# Adafruit_MEMENTO_Camera_Board.net
KiCad netlist of a schematic drawn in EAGLE
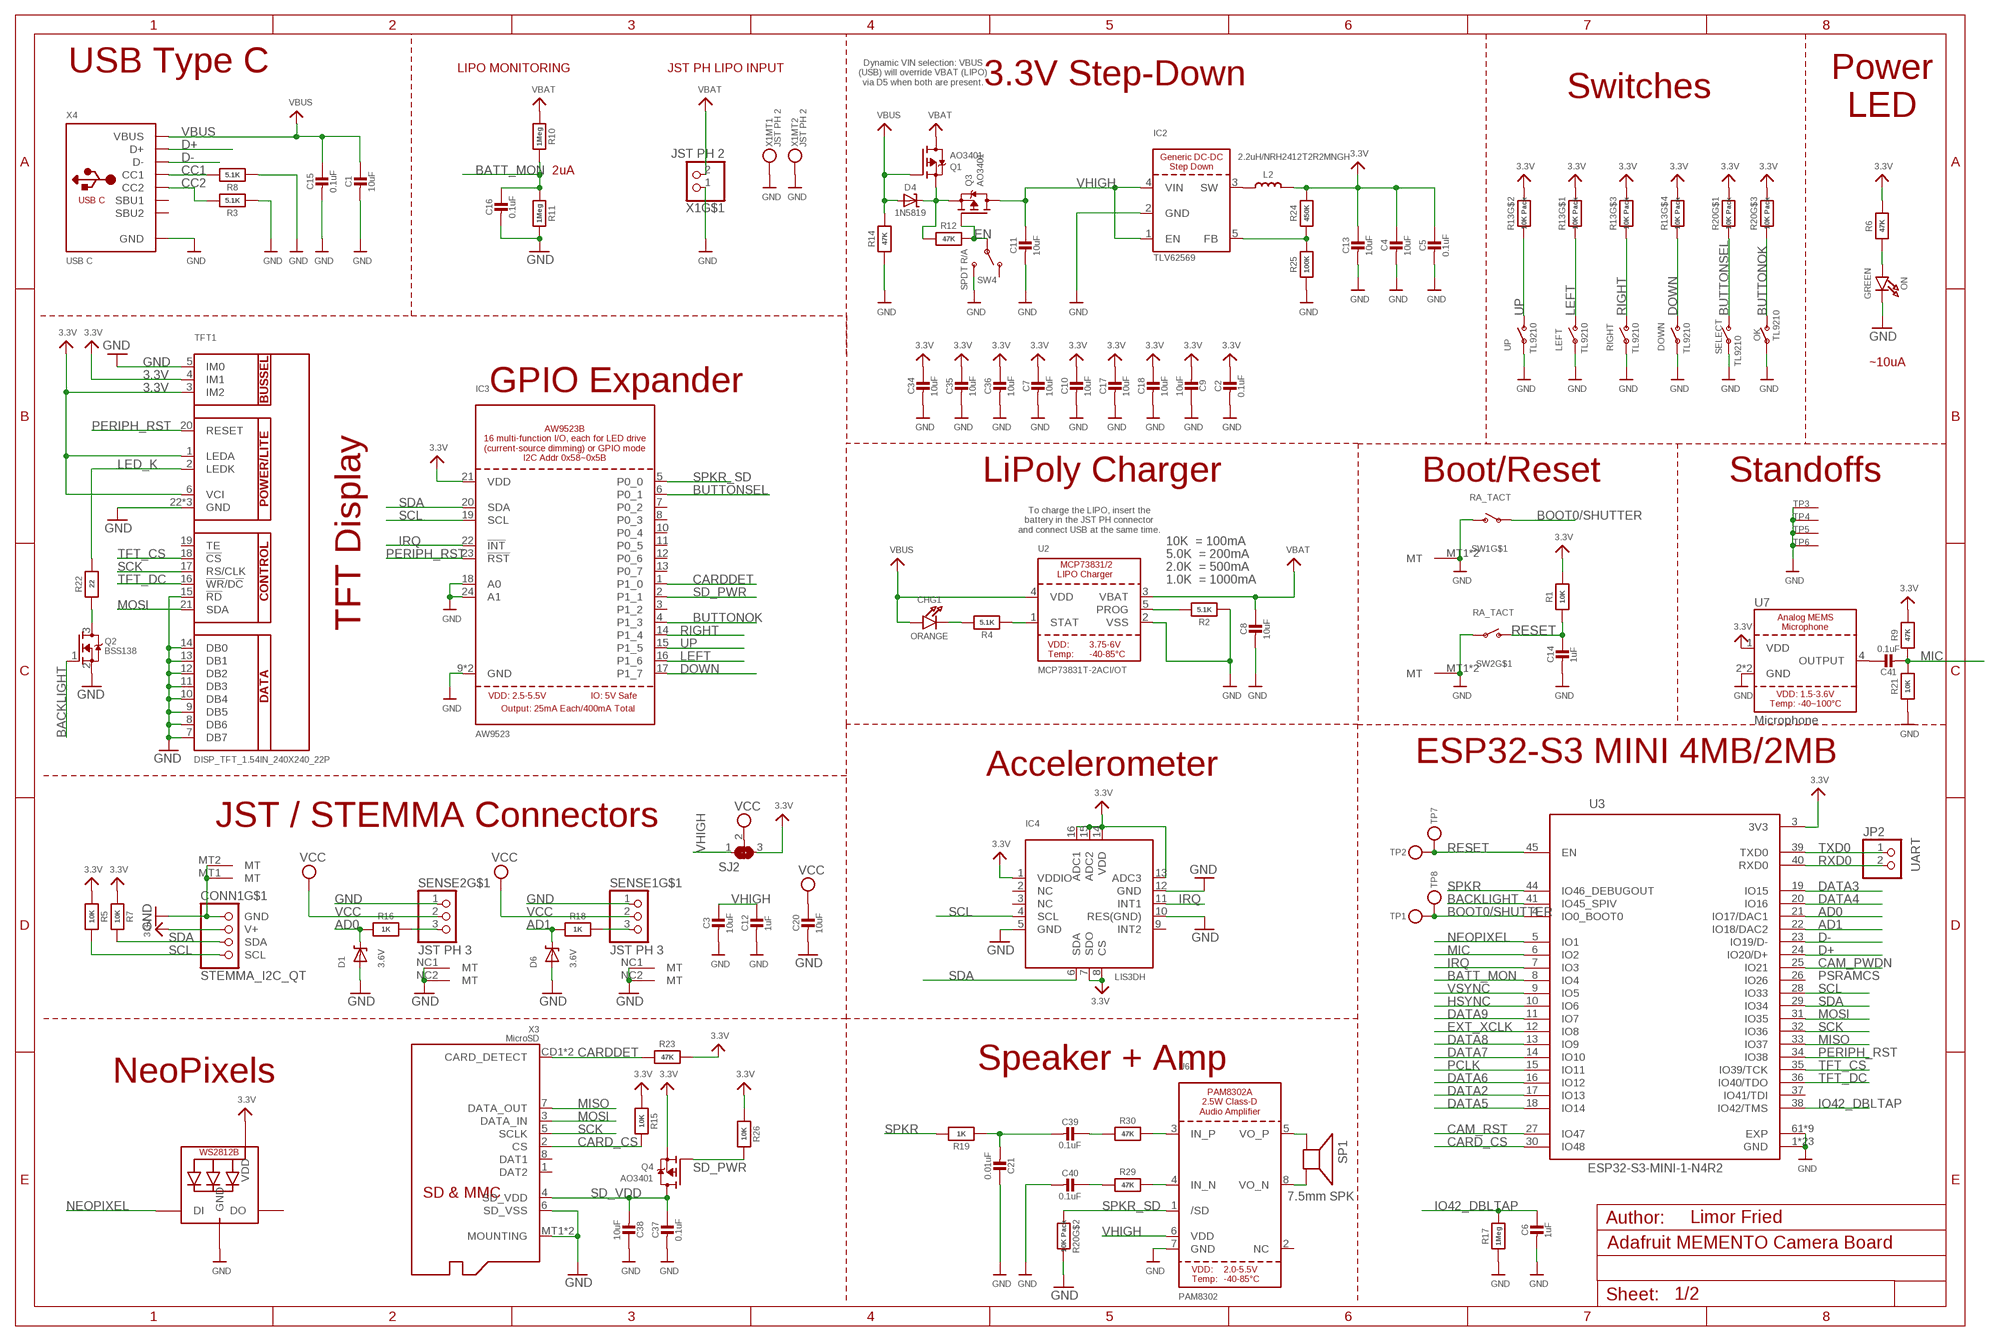
[diagram p0: schematic, sheet 1]
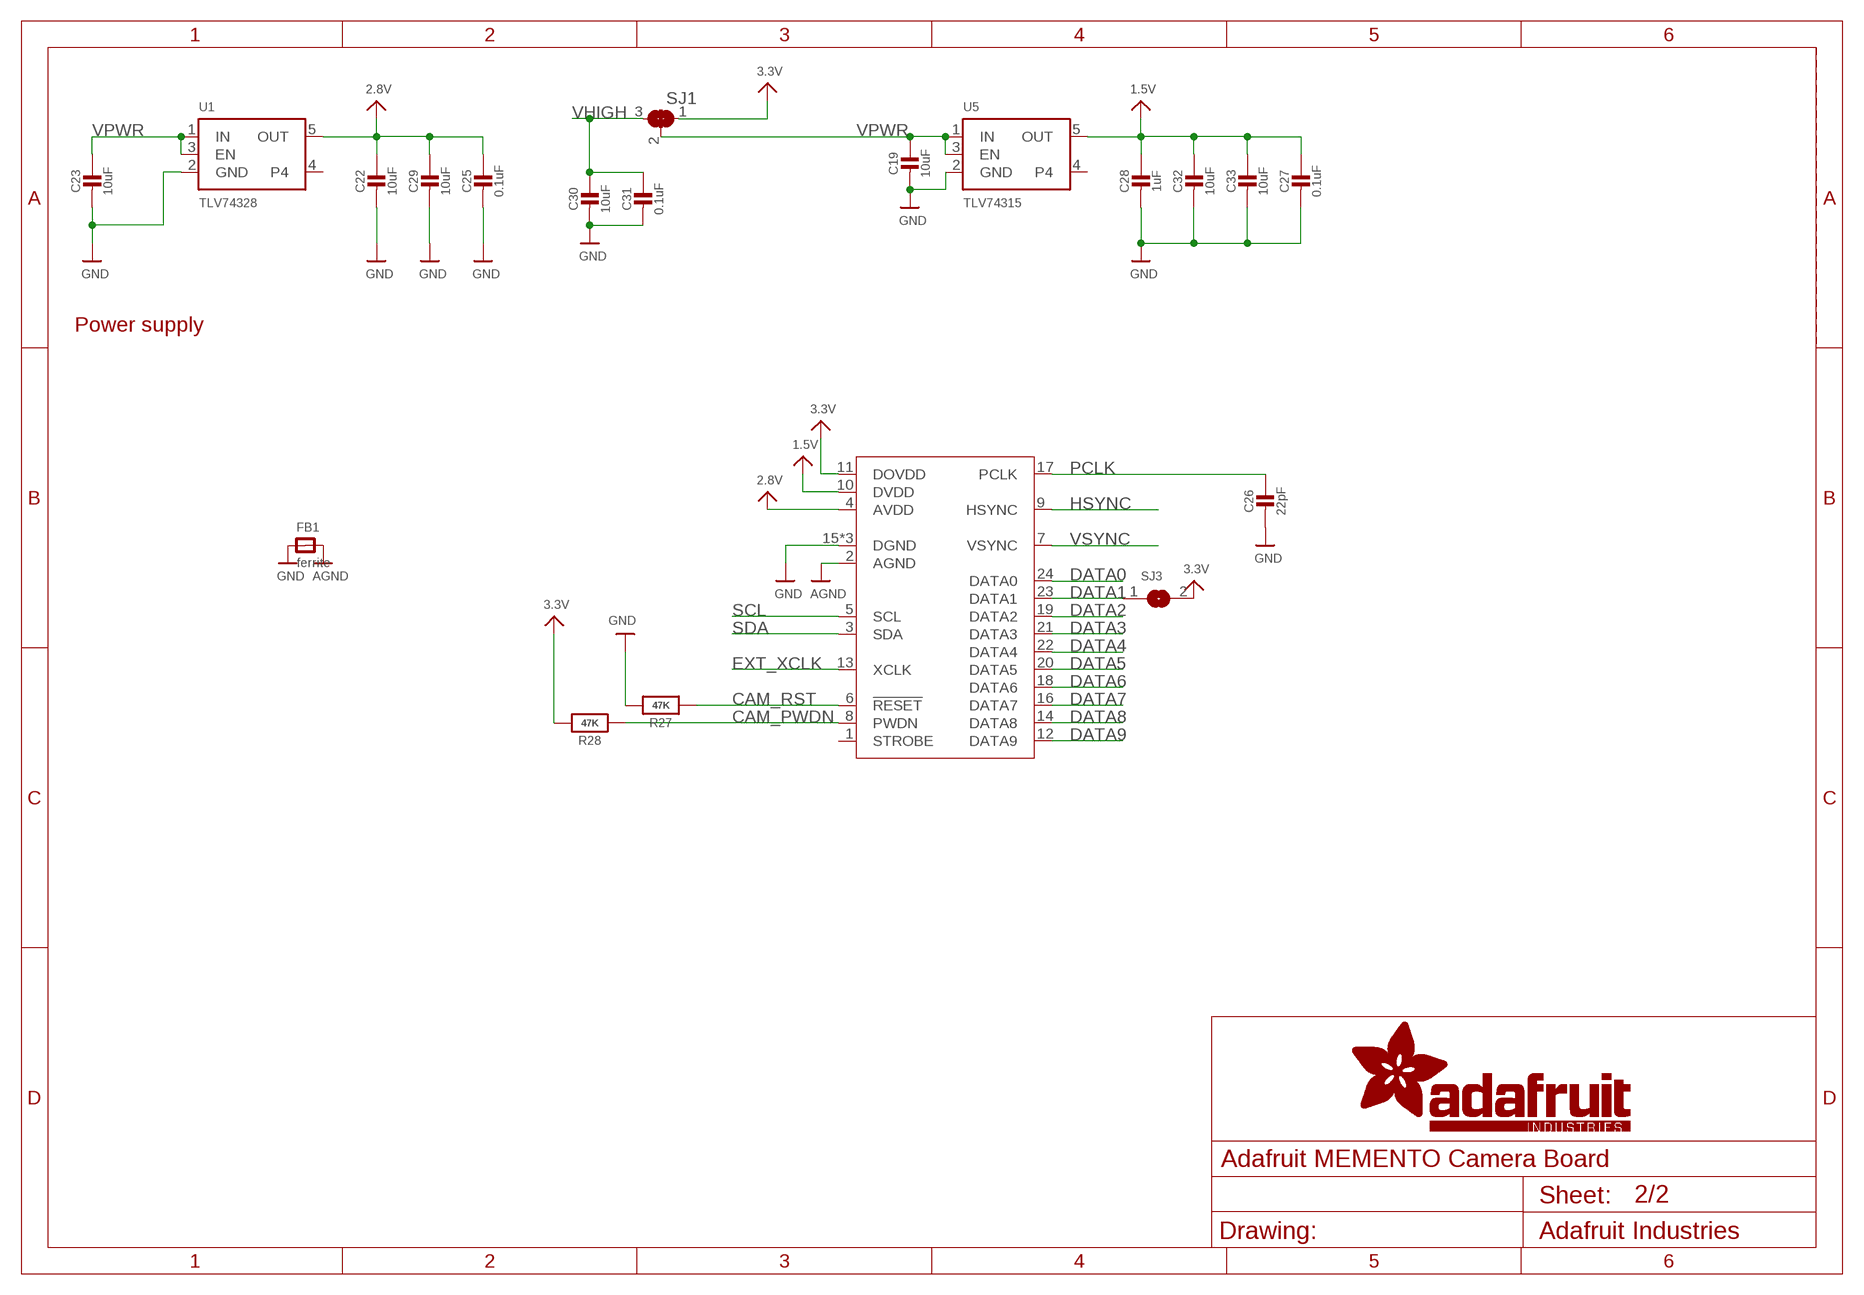
[diagram p1: schematic, sheet 2]

(export (version "E")
  (design (tool "Eeschema 10.0.6"))
  (components
    (comp (ref "C19")
      (value "10uF")
      (footprint "eagle-import:0805-NO")
      (libsource (lib "eagle-import") (part "CAP_CERAMIC0805-NOOUTLINE"))
    )
    (comp (ref "C22")
      (value "10uF")
      (footprint "eagle-import:0805-NO")
      (libsource (lib "eagle-import") (part "CAP_CERAMIC0805-NOOUTLINE"))
    )
    (comp (ref "C23")
      (value "10uF")
      (footprint "eagle-import:0805-NO")
      (libsource (lib "eagle-import") (part "CAP_CERAMIC0805-NOOUTLINE"))
    )
    (comp (ref "C25")
      (value "0.1uF")
      (footprint "eagle-import:0603-NO")
      (libsource (lib "eagle-import") (part "CAP_CERAMIC0603_NO"))
    )
    (comp (ref "C26")
      (value "22pF")
      (footprint "eagle-import:0603-NO")
      (libsource (lib "eagle-import") (part "CAP_CERAMIC0603_NO"))
    )
    (comp (ref "C27")
      (value "0.1uF")
      (footprint "eagle-import:0603-NO")
      (libsource (lib "eagle-import") (part "CAP_CERAMIC0603_NO"))
    )
    (comp (ref "C28")
      (value "1uF")
      (footprint "eagle-import:0603-NO")
      (libsource (lib "eagle-import") (part "CAP_CERAMIC0603_NO"))
    )
    (comp (ref "C29")
      (value "10uF")
      (footprint "eagle-import:0805-NO")
      (libsource (lib "eagle-import") (part "CAP_CERAMIC0805-NOOUTLINE"))
    )
    (comp (ref "C30")
      (value "10uF")
      (footprint "eagle-import:0805-NO")
      (libsource (lib "eagle-import") (part "CAP_CERAMIC0805-NOOUTLINE"))
    )
    (comp (ref "C31")
      (value "0.1uF")
      (footprint "eagle-import:0603-NO")
      (libsource (lib "eagle-import") (part "CAP_CERAMIC0603_NO"))
    )
    (comp (ref "C32")
      (value "10uF")
      (footprint "eagle-import:0805-NO")
      (libsource (lib "eagle-import") (part "CAP_CERAMIC0805-NOOUTLINE"))
    )
    (comp (ref "C33")
      (value "10uF")
      (footprint "eagle-import:0805-NO")
      (libsource (lib "eagle-import") (part "CAP_CERAMIC0805-NOOUTLINE"))
    )
    (comp (ref "FB1")
      (value "ferrite")
      (footprint "eagle-import:0603-NO")
      (libsource (lib "eagle-import") (part "FERRITE-0603NO"))
    )
    (comp (ref "R27")
      (value "47K")
      (footprint "eagle-import:0603-NO")
      (libsource (lib "eagle-import") (part "RESISTOR_0603_NOOUT"))
    )
    (comp (ref "R28")
      (value "47K")
      (footprint "eagle-import:0603-NO")
      (libsource (lib "eagle-import") (part "RESISTOR_0603_NOOUT"))
    )
    (comp (ref "SJ1")
      (value "SOLDERJUMPER_2WAY")
      (footprint "eagle-import:SOLDERJUMPER_2WAY_OPEN_NOPASTE")
      (libsource (lib "eagle-import") (part "SOLDERJUMPER_2WAY"))
    )
    (comp (ref "SJ3")
      (value "SOLDERJUMPERCLOSED")
      (footprint "eagle-import:SOLDERJUMPER_CLOSEDWIRE")
      (libsource (lib "eagle-import") (part "SOLDERJUMPERCLOSED"))
    )
    (comp (ref "U1")
      (value "TLV74328")
      (footprint "eagle-import:SOT23-5")
      (fields (field (name "JLC_ROTATION") "0"))
      (libsource (lib "eagle-import") (part "VREG_SOT23-5"))
    )
    (comp (ref "U5")
      (value "TLV74315")
      (footprint "eagle-import:SOT23-5")
      (fields (field (name "JLC_ROTATION") "0"))
      (libsource (lib "eagle-import") (part "VREG_SOT23-5"))
    )
    (comp (ref "X2")
      (value "CAMERA_OV2640")
      (footprint "eagle-import:OV2640FSL")
      (libsource (lib "eagle-import") (part "CAMERA_OV2640"))
    )
    (comp (ref "C1")
      (value "10uF")
      (footprint "eagle-import:0805-NO")
      (libsource (lib "eagle-import") (part "CAP_CERAMIC0805-NOOUTLINE"))
    )
    (comp (ref "C2")
      (value "0.1uF")
      (footprint "eagle-import:0603-NO")
      (libsource (lib "eagle-import") (part "CAP_CERAMIC0603_NO"))
    )
    (comp (ref "C3")
      (value "10uF")
      (footprint "eagle-import:0805-NO")
      (libsource (lib "eagle-import") (part "CAP_CERAMIC0805-NOOUTLINE"))
    )
    (comp (ref "C4")
      (value "10uF")
      (footprint "eagle-import:0805-NO")
      (libsource (lib "eagle-import") (part "CAP_CERAMIC0805-NOOUTLINE"))
    )
    (comp (ref "C5")
      (value "0.1uF")
      (footprint "eagle-import:0603-NO")
      (libsource (lib "eagle-import") (part "CAP_CERAMIC0603_NO"))
    )
    (comp (ref "C6")
      (value "1uF")
      (footprint "eagle-import:0603-NO")
      (libsource (lib "eagle-import") (part "CAP_CERAMIC0603_NO"))
    )
    (comp (ref "C7")
      (value "10uF")
      (footprint "eagle-import:0805-NO")
      (libsource (lib "eagle-import") (part "CAP_CERAMIC0805-NOOUTLINE"))
    )
    (comp (ref "C8")
      (value "10uF")
      (footprint "eagle-import:0805-NO")
      (libsource (lib "eagle-import") (part "CAP_CERAMIC0805-NOOUTLINE"))
    )
    (comp (ref "C9")
      (value "10uF")
      (footprint "eagle-import:0805-NO")
      (libsource (lib "eagle-import") (part "CAP_CERAMIC0805-NOOUTLINE"))
    )
    (comp (ref "C10")
      (value "10uF")
      (footprint "eagle-import:0805-NO")
      (libsource (lib "eagle-import") (part "CAP_CERAMIC0805-NOOUTLINE"))
    )
    (comp (ref "C11")
      (value "10uF")
      (footprint "eagle-import:0805-NO")
      (libsource (lib "eagle-import") (part "CAP_CERAMIC0805-NOOUTLINE"))
    )
    (comp (ref "C12")
      (value "1uF")
      (footprint "eagle-import:0603-NO")
      (libsource (lib "eagle-import") (part "CAP_CERAMIC0603_NO"))
    )
    (comp (ref "C13")
      (value "10uF")
      (footprint "eagle-import:0805-NO")
      (libsource (lib "eagle-import") (part "CAP_CERAMIC0805-NOOUTLINE"))
    )
    (comp (ref "C14")
      (value "1uF")
      (footprint "eagle-import:0603-NO")
      (libsource (lib "eagle-import") (part "CAP_CERAMIC0603_NO"))
    )
    (comp (ref "C15")
      (value "0.1uF")
      (footprint "eagle-import:0603-NO")
      (libsource (lib "eagle-import") (part "CAP_CERAMIC0603_NO"))
    )
    (comp (ref "C16")
      (value "0.1uF")
      (footprint "eagle-import:0603-NO")
      (libsource (lib "eagle-import") (part "CAP_CERAMIC0603_NO"))
    )
    (comp (ref "C17")
      (value "10uF")
      (footprint "eagle-import:0805-NO")
      (libsource (lib "eagle-import") (part "CAP_CERAMIC0805-NOOUTLINE"))
    )
    (comp (ref "C18")
      (value "10uF")
      (footprint "eagle-import:0805-NO")
      (libsource (lib "eagle-import") (part "CAP_CERAMIC0805-NOOUTLINE"))
    )
    (comp (ref "C20")
      (value "10uF")
      (footprint "eagle-import:0805-NO")
      (libsource (lib "eagle-import") (part "CAP_CERAMIC0805-NOOUTLINE"))
    )
    (comp (ref "C21")
      (value "0.01uF")
      (footprint "eagle-import:0603-NO")
      (libsource (lib "eagle-import") (part "CAP_CERAMIC0603_NO"))
    )
    (comp (ref "C34")
      (value "10uF")
      (footprint "eagle-import:0805-NO")
      (libsource (lib "eagle-import") (part "CAP_CERAMIC0805-NOOUTLINE"))
    )
    (comp (ref "C35")
      (value "10uF")
      (footprint "eagle-import:0805-NO")
      (libsource (lib "eagle-import") (part "CAP_CERAMIC0805-NOOUTLINE"))
    )
    (comp (ref "C36")
      (value "10uF")
      (footprint "eagle-import:0805-NO")
      (libsource (lib "eagle-import") (part "CAP_CERAMIC0805-NOOUTLINE"))
    )
    (comp (ref "C37")
      (value "0.1uF")
      (footprint "eagle-import:0603-NO")
      (libsource (lib "eagle-import") (part "CAP_CERAMIC0603_NO"))
    )
    (comp (ref "C38")
      (value "10uF")
      (footprint "eagle-import:0805-NO")
      (libsource (lib "eagle-import") (part "CAP_CERAMIC0805-NOOUTLINE"))
    )
    (comp (ref "C39")
      (value "0.1uF")
      (footprint "eagle-import:0603-NO")
      (libsource (lib "eagle-import") (part "CAP_CERAMIC0603_NO"))
    )
    (comp (ref "C40")
      (value "0.1uF")
      (footprint "eagle-import:0603-NO")
      (libsource (lib "eagle-import") (part "CAP_CERAMIC0603_NO"))
    )
    (comp (ref "C41")
      (value "0.1uF")
      (footprint "eagle-import:0603-NO")
      (libsource (lib "eagle-import") (part "CAP_CERAMIC0603_NO"))
    )
    (comp (ref "CHG1")
      (value "ORANGE")
      (footprint "eagle-import:CHIPLED_0603_NOOUTLINE")
      (libsource (lib "eagle-import") (part "LED0603_NOOUTLINE"))
    )
    (comp (ref "CONN1")
      (value "STEMMA_I2C_QT")
      (footprint "eagle-import:JST_SH4")
      (libsource (lib "eagle-import") (part "STEMMA_I2C_QT"))
    )
    (comp (ref "D1")
      (value "3.6V")
      (footprint "eagle-import:SOD-323")
      (libsource (lib "eagle-import") (part "DIODE-ZENERSOD323"))
    )
    (comp (ref "D4")
      (value "1N5819")
      (footprint "eagle-import:SOD-123")
      (libsource (lib "eagle-import") (part "DIODE-SCHOTTKYSOD-123"))
    )
    (comp (ref "D6")
      (value "3.6V")
      (footprint "eagle-import:SOD-323")
      (libsource (lib "eagle-import") (part "DIODE-ZENERSOD323"))
    )
    (comp (ref "DOWN")
      (value "TL9210")
      (footprint "eagle-import:TL9210")
      (libsource (lib "eagle-import") (part "SWITCH_SPST_NOMNT_TL9210"))
    )
    (comp (ref "IC2")
      (value "TLV62569")
      (footprint "eagle-import:SOT23-5")
      (libsource (lib "eagle-import") (part "VREG_BUCK_5PIN_AP3429/A"))
    )
    (comp (ref "IC3")
      (value "AW9523")
      (footprint "eagle-import:QFN24_4MM_SMSC")
      (libsource (lib "eagle-import") (part "AW9523"))
    )
    (comp (ref "IC4")
      (value "LIS3DH")
      (footprint "eagle-import:LGA16_3X3MM")
      (libsource (lib "eagle-import") (part "ACCEL_LIS3DHTR"))
    )
    (comp (ref "JP2")
      (value "UART")
      (footprint "eagle-import:1X02_ROUND")
      (libsource (lib "eagle-import") (part "HEADER-1X2ROUND"))
    )
    (comp (ref "L2")
      (value "2.2uH/NRH2412T2R2MNGH")
      (footprint "eagle-import:INDUCTOR_TAIYOYUDEN_NR3015")
      (libsource (lib "eagle-import") (part "INDUCTORNR3015"))
    )
    (comp (ref "LED2")
      (value "WS2812B_SK6805_1515")
      (footprint "eagle-import:SK6805_1515")
      (libsource (lib "eagle-import") (part "WS2812B_SK6805_1515"))
    )
    (comp (ref "LEFT")
      (value "TL9210")
      (footprint "eagle-import:TL9210")
      (libsource (lib "eagle-import") (part "SWITCH_SPST_NOMNT_TL9210"))
    )
    (comp (ref "OK")
      (value "TL9210")
      (footprint "eagle-import:TL9210")
      (libsource (lib "eagle-import") (part "SWITCH_SPST_NOMNT_TL9210"))
    )
    (comp (ref "ON")
      (value "GREEN")
      (footprint "eagle-import:CHIPLED_0603_NOOUTLINE")
      (libsource (lib "eagle-import") (part "LED0603_NOOUTLINE"))
    )
    (comp (ref "Q1")
      (value "AO3401")
      (footprint "eagle-import:SOT23-R")
      (libsource (lib "eagle-import") (part "MOSFET-P"))
    )
    (comp (ref "Q2")
      (value "BSS138")
      (footprint "eagle-import:SOT23-WIDE")
      (libsource (lib "eagle-import") (part "MOSFET-NWIDE"))
    )
    (comp (ref "Q3")
      (value "AO3401")
      (footprint "eagle-import:SOT23-R")
      (libsource (lib "eagle-import") (part "MOSFET-P"))
    )
    (comp (ref "Q4")
      (value "AO3401")
      (footprint "eagle-import:SOT23-R")
      (libsource (lib "eagle-import") (part "MOSFET-P"))
    )
    (comp (ref "R1")
      (value "10K")
      (footprint "eagle-import:0603-NO")
      (libsource (lib "eagle-import") (part "RESISTOR_0603_NOOUT"))
    )
    (comp (ref "R2")
      (value "5.1K")
      (footprint "eagle-import:0603-NO")
      (libsource (lib "eagle-import") (part "RESISTOR_0603_NOOUT"))
    )
    (comp (ref "R3")
      (value "5.1K")
      (footprint "eagle-import:0603-NO")
      (libsource (lib "eagle-import") (part "RESISTOR_0603_NOOUT"))
    )
    (comp (ref "R4")
      (value "5.1K")
      (footprint "eagle-import:0603-NO")
      (libsource (lib "eagle-import") (part "RESISTOR_0603_NOOUT"))
    )
    (comp (ref "R5")
      (value "10K")
      (footprint "eagle-import:0603-NO")
      (libsource (lib "eagle-import") (part "RESISTOR_0603_NOOUT"))
    )
    (comp (ref "R6")
      (value "47K")
      (footprint "eagle-import:0603-NO")
      (libsource (lib "eagle-import") (part "RESISTOR_0603_NOOUT"))
    )
    (comp (ref "R7")
      (value "10K")
      (footprint "eagle-import:0603-NO")
      (libsource (lib "eagle-import") (part "RESISTOR_0603_NOOUT"))
    )
    (comp (ref "R8")
      (value "5.1K")
      (footprint "eagle-import:0603-NO")
      (libsource (lib "eagle-import") (part "RESISTOR_0603_NOOUT"))
    )
    (comp (ref "R9")
      (value "47K")
      (footprint "eagle-import:0603-NO")
      (libsource (lib "eagle-import") (part "RESISTOR_0603_NOOUT"))
    )
    (comp (ref "R10")
      (value "1Meg")
      (footprint "eagle-import:0603-NO")
      (libsource (lib "eagle-import") (part "RESISTOR_0603_NOOUT"))
    )
    (comp (ref "R11")
      (value "1Meg")
      (footprint "eagle-import:0603-NO")
      (libsource (lib "eagle-import") (part "RESISTOR_0603_NOOUT"))
    )
    (comp (ref "R12")
      (value "47K")
      (footprint "eagle-import:0603-NO")
      (libsource (lib "eagle-import") (part "RESISTOR_0603_NOOUT"))
    )
    (comp (ref "R13")
      (value "10K Pack")
      (footprint "eagle-import:RESPACK_4X0603")
      (libsource (lib "eagle-import") (part "RESISTOR_4PACK"))
    )
    (comp (ref "R14")
      (value "47K")
      (footprint "eagle-import:0603-NO")
      (libsource (lib "eagle-import") (part "RESISTOR_0603_NOOUT"))
    )
    (comp (ref "R15")
      (value "10K")
      (footprint "eagle-import:0603-NO")
      (libsource (lib "eagle-import") (part "RESISTOR_0603_NOOUT"))
    )
    (comp (ref "R16")
      (value "1K")
      (footprint "eagle-import:0603-NO")
      (libsource (lib "eagle-import") (part "RESISTOR_0603_NOOUT"))
    )
    (comp (ref "R17")
      (value "1Meg")
      (footprint "eagle-import:0603-NO")
      (libsource (lib "eagle-import") (part "RESISTOR_0603_NOOUT"))
    )
    (comp (ref "R18")
      (value "1K")
      (footprint "eagle-import:0603-NO")
      (libsource (lib "eagle-import") (part "RESISTOR_0603_NOOUT"))
    )
    (comp (ref "R19")
      (value "1K")
      (footprint "eagle-import:0603-NO")
      (libsource (lib "eagle-import") (part "RESISTOR_0603_NOOUT"))
    )
    (comp (ref "R20")
      (value "10K Pack")
      (footprint "eagle-import:RESPACK_4X0603")
      (libsource (lib "eagle-import") (part "RESISTOR_4PACK"))
    )
    (comp (ref "R21")
      (value "10K")
      (footprint "eagle-import:0603-NO")
      (libsource (lib "eagle-import") (part "RESISTOR_0603_NOOUT"))
    )
    (comp (ref "R22")
      (value "22")
      (footprint "eagle-import:0603-NO")
      (libsource (lib "eagle-import") (part "RESISTOR_0603_NOOUT"))
    )
    (comp (ref "R23")
      (value "47K")
      (footprint "eagle-import:0603-NO")
      (libsource (lib "eagle-import") (part "RESISTOR_0603_NOOUT"))
    )
    (comp (ref "R24")
      (value "450K")
      (footprint "eagle-import:0603-NO")
      (libsource (lib "eagle-import") (part "RESISTOR_0603_NOOUT"))
    )
    (comp (ref "R25")
      (value "100K")
      (footprint "eagle-import:0603-NO")
      (libsource (lib "eagle-import") (part "RESISTOR_0603_NOOUT"))
    )
    (comp (ref "R26")
      (value "10K")
      (footprint "eagle-import:0603-NO")
      (libsource (lib "eagle-import") (part "RESISTOR_0603_NOOUT"))
    )
    (comp (ref "R29")
      (value "47K")
      (footprint "eagle-import:0603-NO")
      (libsource (lib "eagle-import") (part "RESISTOR_0603_NOOUT"))
    )
    (comp (ref "R30")
      (value "47K")
      (footprint "eagle-import:0603-NO")
      (libsource (lib "eagle-import") (part "RESISTOR_0603_NOOUT"))
    )
    (comp (ref "RIGHT")
      (value "TL9210")
      (footprint "eagle-import:TL9210")
      (libsource (lib "eagle-import") (part "SWITCH_SPST_NOMNT_TL9210"))
    )
    (comp (ref "SELECT")
      (value "TL9210")
      (footprint "eagle-import:TL9210")
      (libsource (lib "eagle-import") (part "SWITCH_SPST_NOMNT_TL9210"))
    )
    (comp (ref "SENSE1")
      (value "JST PH 3")
      (footprint "eagle-import:JSTPH3")
      (libsource (lib "eagle-import") (part "CON_JST_PH_3PIN"))
    )
    (comp (ref "SENSE2")
      (value "JST PH 3")
      (footprint "eagle-import:JSTPH3")
      (libsource (lib "eagle-import") (part "CON_JST_PH_3PIN"))
    )
    (comp (ref "SJ2")
      (value "SOLDERJUMPER_2WAY")
      (footprint "eagle-import:SOLDERJUMPER_2WAY_OPEN_NOPASTE")
      (libsource (lib "eagle-import") (part "SOLDERJUMPER_2WAY"))
    )
    (comp (ref "SP1")
      (value "7.5mm SPK")
      (footprint "eagle-import:BUZZER_SMT_7.5MM")
      (libsource (lib "eagle-import") (part "SPEAKER_7.5MM"))
    )
    (comp (ref "SW1")
      (value "RA_TACT")
      (footprint "eagle-import:SPST_TACTILE_RA")
      (libsource (lib "eagle-import") (part "SWITCH_SPST_MNT_TACT_RA"))
    )
    (comp (ref "SW2")
      (value "RA_TACT")
      (footprint "eagle-import:SPST_TACTILE_RA")
      (libsource (lib "eagle-import") (part "SWITCH_SPST_MNT_TACT_RA"))
    )
    (comp (ref "SW4")
      (value "SPDT R/A")
      (footprint "eagle-import:SPDT_SMT_SSSS811101")
      (libsource (lib "eagle-import") (part "SWITCH_SPDT"))
    )
    (comp (ref "TFT1")
      (value "DISP_TFT_1.54IN_240X240_22P")
      (footprint "eagle-import:TFT_1.54IN_240X240_22PIN")
      (libsource (lib "eagle-import") (part "DISP_TFT_1.54IN_240X240_22P"))
    )
    (comp (ref "TP1")
      (value "TESTPOINTROUND1.5MMNO")
      (footprint "eagle-import:TESTPOINT_ROUND_1.5MM_NO")
      (libsource (lib "eagle-import") (part "TESTPOINTROUND1.5MMNO"))
    )
    (comp (ref "TP2")
      (value "TESTPOINTROUND1.5MMNO")
      (footprint "eagle-import:TESTPOINT_ROUND_1.5MM_NO")
      (libsource (lib "eagle-import") (part "TESTPOINTROUND1.5MMNO"))
    )
    (comp (ref "TP3")
      (value "SEWTAP_SMTNUTM3")
      (footprint "eagle-import:SMT_NUT_3MM")
      (libsource (lib "eagle-import") (part "SEWTAP_SMTNUTM3"))
    )
    (comp (ref "TP4")
      (value "SEWTAP_SMTNUTM3")
      (footprint "eagle-import:SMT_NUT_3MM")
      (libsource (lib "eagle-import") (part "SEWTAP_SMTNUTM3"))
    )
    (comp (ref "TP5")
      (value "SEWTAP_SMTNUTM3")
      (footprint "eagle-import:SMT_NUT_3MM")
      (libsource (lib "eagle-import") (part "SEWTAP_SMTNUTM3"))
    )
    (comp (ref "TP6")
      (value "SEWTAP_SMTNUTM3")
      (footprint "eagle-import:SMT_NUT_3MM")
      (libsource (lib "eagle-import") (part "SEWTAP_SMTNUTM3"))
    )
    (comp (ref "TP7")
      (value "TESTPOINTROUND1.5MMNO")
      (footprint "eagle-import:TESTPOINT_ROUND_1.5MM_NO")
      (libsource (lib "eagle-import") (part "TESTPOINTROUND1.5MMNO"))
    )
    (comp (ref "TP8")
      (value "TESTPOINTROUND1.5MMNO")
      (footprint "eagle-import:TESTPOINT_ROUND_1.5MM_NO")
      (libsource (lib "eagle-import") (part "TESTPOINTROUND1.5MMNO"))
    )
    (comp (ref "U2")
      (value "MCP73831T-2ACI/OT")
      (footprint "eagle-import:SOT23-5")
      (libsource (lib "eagle-import") (part "MCP73831/2"))
    )
    (comp (ref "U3")
      (value "ESP32-S3-MINI-1-N4R2")
      (footprint "eagle-import:ESP32-S2-MINI-1")
      (fields
        (field (name "MANUFACTURER_PART_NUMBER") "ESP32-S2-MINI-1")
        (field (name "COPYRIGHT") "Copyright (C) 2018 Accelerated Designs. All rights reserved")
      )
      (libsource (lib "eagle-import") (part "ESP32-S3-MINI-1"))
    )
    (comp (ref "U6")
      (value "PAM8302")
      (footprint "eagle-import:MSOP8_0.65MM")
      (libsource (lib "eagle-import") (part "AUDIOAMP_PAM8302A"))
    )
    (comp (ref "U7")
      (value "Microphone")
      (footprint "eagle-import:MEMS_MIC_2.75X1.85")
      (libsource (lib "eagle-import") (part "ANALOG_MEMS_MIC_2.75X1.85"))
    )
    (comp (ref "UP")
      (value "TL9210")
      (footprint "eagle-import:TL9210")
      (libsource (lib "eagle-import") (part "SWITCH_SPST_NOMNT_TL9210"))
    )
    (comp (ref "X1")
      (value "JST PH 2")
      (footprint "eagle-import:JSTPH2_BATT")
      (libsource (lib "eagle-import") (part "CON_JST_PH_2PIN_MT_BATT"))
    )
    (comp (ref "X3")
      (value "MicroSD")
      (footprint "eagle-import:MICROSD")
      (libsource (lib "eagle-import") (part "MICROSD"))
    )
    (comp (ref "X4")
      (value "USB C")
      (footprint "eagle-import:USB_C_CUSB31-CFM2AX-01-X")
      (libsource (lib "eagle-import") (part "USB_C"))
    )
  )
  (nets
    (net (code "1") (name "1.5V") (class "Default")
      (node (ref "C27") (pin "1") (pinfunction "1_1") (pintype "passive"))
      (node (ref "C28") (pin "1") (pinfunction "1_1") (pintype "passive"))
      (node (ref "C32") (pin "1") (pinfunction "1_1") (pintype "passive"))
      (node (ref "C33") (pin "1") (pinfunction "1_1") (pintype "passive"))
      (node (ref "U5") (pin "5") (pinfunction "OUT_5") (pintype "power_in"))
      (node (ref "X2") (pin "10") (pinfunction "DVDD_10") (pintype "power_in"))
    )
    (net (code "2") (name "2.8V") (class "Default")
      (node (ref "C22") (pin "1") (pinfunction "1_1") (pintype "passive"))
      (node (ref "C25") (pin "1") (pinfunction "1_1") (pintype "passive"))
      (node (ref "C29") (pin "1") (pinfunction "1_1") (pintype "passive"))
      (node (ref "U1") (pin "5") (pinfunction "OUT_5") (pintype "power_in"))
      (node (ref "X2") (pin "4") (pinfunction "AVDD_4") (pintype "power_in"))
    )
    (net (code "3") (name "3.3V") (class "Default")
      (node (ref "C10") (pin "1") (pinfunction "1_1") (pintype "passive"))
      (node (ref "C13") (pin "1") (pinfunction "1_1") (pintype "passive"))
      (node (ref "C17") (pin "1") (pinfunction "1_1") (pintype "passive"))
      (node (ref "C18") (pin "1") (pinfunction "1_1") (pintype "passive"))
      (node (ref "C2") (pin "1") (pinfunction "1_1") (pintype "passive"))
      (node (ref "C34") (pin "1") (pinfunction "1_1") (pintype "passive"))
      (node (ref "C35") (pin "1") (pinfunction "1_1") (pintype "passive"))
      (node (ref "C36") (pin "1") (pinfunction "1_1") (pintype "passive"))
      (node (ref "C4") (pin "1") (pinfunction "1_1") (pintype "passive"))
      (node (ref "C5") (pin "1") (pinfunction "1_1") (pintype "passive"))
      (node (ref "C7") (pin "1") (pinfunction "1_1") (pintype "passive"))
      (node (ref "C9") (pin "2") (pinfunction "2_2") (pintype "passive"))
      (node (ref "CONN1") (pin "2") (pinfunction "V+_2") (pintype "passive"))
      (node (ref "IC3") (pin "21") (pinfunction "VDD_21") (pintype "power_in"))
      (node (ref "IC4") (pin "1") (pinfunction "VDDIO_1") (pintype "power_in"))
      (node (ref "IC4") (pin "13") (pinfunction "ADC3_13") (pintype "input"))
      (node (ref "IC4") (pin "14") (pinfunction "VDD_14") (pintype "power_in"))
      (node (ref "IC4") (pin "15") (pinfunction "ADC2_15") (pintype "input"))
      (node (ref "IC4") (pin "16") (pinfunction "ADC1_16") (pintype "input"))
      (node (ref "IC4") (pin "7") (pinfunction "SDO_7") (pintype "bidirectional"))
      (node (ref "IC4") (pin "8") (pinfunction "CS_8") (pintype "input"))
      (node (ref "L2") (pin "P$2") (pinfunction "2_P$2") (pintype "passive"))
      (node (ref "LED2") (pin "2") (pinfunction "VDD_2") (pintype "power_in"))
      (node (ref "Q4") (pin "2") (pinfunction "S_2") (pintype "passive"))
      (node (ref "R1") (pin "2") (pinfunction "2_2") (pintype "passive"))
      (node (ref "R13") (pin "5") (pinfunction "2_5") (pintype "passive"))
      (node (ref "R13") (pin "6") (pinfunction "2_6") (pintype "passive"))
      (node (ref "R13") (pin "7") (pinfunction "2_7") (pintype "passive"))
      (node (ref "R13") (pin "8") (pinfunction "2_8") (pintype "passive"))
      (node (ref "R15") (pin "2") (pinfunction "2_2") (pintype "passive"))
      (node (ref "R20") (pin "6") (pinfunction "2_6") (pintype "passive"))
      (node (ref "R20") (pin "8") (pinfunction "2_8") (pintype "passive"))
      (node (ref "R23") (pin "2") (pinfunction "2_2") (pintype "passive"))
      (node (ref "R24") (pin "2") (pinfunction "2_2") (pintype "passive"))
      (node (ref "R26") (pin "1") (pinfunction "1_1") (pintype "passive"))
      (node (ref "R28") (pin "2") (pinfunction "2_2") (pintype "passive"))
      (node (ref "R5") (pin "1") (pinfunction "1_1") (pintype "passive"))
      (node (ref "R6") (pin "2") (pinfunction "2_2") (pintype "passive"))
      (node (ref "R7") (pin "1") (pinfunction "1_1") (pintype "passive"))
      (node (ref "R9") (pin "2") (pinfunction "2_2") (pintype "passive"))
      (node (ref "SJ1") (pin "1") (pinfunction "1_1") (pintype "passive"))
      (node (ref "SJ2") (pin "3") (pinfunction "3_3") (pintype "passive"))
      (node (ref "SJ3") (pin "2") (pinfunction "2_2") (pintype "passive"))
      (node (ref "TFT1") (pin "1") (pinfunction "LEDA_1") (pintype "input"))
      (node (ref "TFT1") (pin "3") (pinfunction "IM2_3") (pintype "input"))
      (node (ref "TFT1") (pin "4") (pinfunction "IM1_4") (pintype "input"))
      (node (ref "TFT1") (pin "6") (pinfunction "VCI_6") (pintype "power_in"))
      (node (ref "U3") (pin "3") (pinfunction "3V3_3") (pintype "power_in"))
      (node (ref "U7") (pin "1") (pinfunction "VDD_1") (pintype "power_in"))
      (node (ref "X2") (pin "11") (pinfunction "DOVDD_11") (pintype "power_in"))
    )
    (net (code "4") (name "AD0") (class "Default")
      (node (ref "D1") (pin "C") (pinfunction "C_C") (pintype "passive"))
      (node (ref "R16") (pin "2") (pinfunction "2_2") (pintype "passive"))
      (node (ref "U3") (pin "21") (pinfunction "IO17/DAC1_21") (pintype "bidirectional"))
    )
    (net (code "5") (name "AD1") (class "Default")
      (node (ref "D6") (pin "C") (pinfunction "C_C") (pintype "passive"))
      (node (ref "R18") (pin "2") (pinfunction "2_2") (pintype "passive"))
      (node (ref "U3") (pin "22") (pinfunction "IO18/DAC2_22") (pintype "bidirectional"))
    )
    (net (code "6") (name "AGND") (class "Default")
      (node (ref "FB1") (pin "2") (pinfunction "P$2_2") (pintype "passive"))
      (node (ref "X2") (pin "2") (pinfunction "AGND_2") (pintype "power_in"))
    )
    (net (code "7") (name "BACKLIGHT") (class "Default")
      (node (ref "Q2") (pin "1") (pinfunction "G_1") (pintype "bidirectional"))
      (node (ref "U3") (pin "41") (pinfunction "IO45_SPIV_41") (pintype "bidirectional"))
    )
    (net (code "8") (name "BATT_MON") (class "Default")
      (node (ref "C16") (pin "1") (pinfunction "1_1") (pintype "passive"))
      (node (ref "R10") (pin "2") (pinfunction "2_2") (pintype "passive"))
      (node (ref "R11") (pin "1") (pinfunction "1_1") (pintype "passive"))
      (node (ref "U3") (pin "8") (pinfunction "IO4_8") (pintype "bidirectional"))
    )
    (net (code "9") (name "BOOT0{slash}SHUTTER") (class "Default")
      (node (ref "SW1") (pin "1") (pinfunction "P_1") (pintype "passive"))
      (node (ref "TP1") (pin "P$1") (pinfunction "P$1_P$1") (pintype "bidirectional"))
      (node (ref "TP8") (pin "P$1") (pinfunction "P$1_P$1") (pintype "bidirectional"))
      (node (ref "U3") (pin "4") (pinfunction "IO0_BOOT0_4") (pintype "bidirectional"))
    )
    (net (code "10") (name "BUTTONOK") (class "Default")
      (node (ref "IC3") (pin "4") (pinfunction "P1_3_4") (pintype "bidirectional"))
      (node (ref "OK") (pin "2") (pinfunction "S_2") (pintype "passive"))
      (node (ref "R20") (pin "3") (pinfunction "1_3") (pintype "passive"))
    )
    (net (code "11") (name "BUTTONSEL") (class "Default")
      (node (ref "IC3") (pin "6") (pinfunction "P0_1_6") (pintype "bidirectional"))
      (node (ref "R20") (pin "1") (pinfunction "1_1") (pintype "passive"))
      (node (ref "SELECT") (pin "2") (pinfunction "S_2") (pintype "passive"))
    )
    (net (code "12") (name "CAM_PWDN") (class "Default")
      (node (ref "R28") (pin "1") (pinfunction "1_1") (pintype "passive"))
      (node (ref "U3") (pin "25") (pinfunction "IO21_25") (pintype "bidirectional"))
      (node (ref "X2") (pin "8") (pinfunction "PWDN_8") (pintype "input"))
    )
    (net (code "13") (name "CAM_RST") (class "Default")
      (node (ref "R27") (pin "1") (pinfunction "1_1") (pintype "passive"))
      (node (ref "U3") (pin "27") (pinfunction "IO47_27") (pintype "bidirectional"))
      (node (ref "X2") (pin "6") (pinfunction "~{RESET}_6") (pintype "input"))
    )
    (net (code "14") (name "CARDDET") (class "Default")
      (node (ref "IC3") (pin "1") (pinfunction "P1_0_1") (pintype "bidirectional"))
      (node (ref "R23") (pin "1") (pinfunction "1_1") (pintype "passive"))
      (node (ref "X3") (pin "CD1") (pinfunction "CARD_DETECT_CD1") (pintype "passive"))
      (node (ref "X3") (pin "CD2") (pinfunction "CARD_DETECT_CD2") (pintype "passive"))
    )
    (net (code "15") (name "CARD_CS") (class "Default")
      (node (ref "R15") (pin "1") (pinfunction "1_1") (pintype "passive"))
      (node (ref "U3") (pin "30") (pinfunction "IO48_30") (pintype "bidirectional"))
      (node (ref "X3") (pin "2") (pinfunction "CS_2") (pintype "input"))
    )
    (net (code "16") (name "CC1") (class "Default")
      (node (ref "R8") (pin "2") (pinfunction "2_2") (pintype "passive"))
      (node (ref "X4") (pin "A5") (pinfunction "CC1_A5") (pintype "bidirectional"))
    )
    (net (code "17") (name "CC2") (class "Default")
      (node (ref "R3") (pin "2") (pinfunction "2_2") (pintype "passive"))
      (node (ref "X4") (pin "B5") (pinfunction "CC2_B5") (pintype "bidirectional"))
    )
    (net (code "18") (name "D+") (class "Default")
      (node (ref "U3") (pin "24") (pinfunction "IO20/D+_24") (pintype "bidirectional"))
      (node (ref "X4") (pin "A6") (pinfunction "D+_A6") (pintype "bidirectional"))
      (node (ref "X4") (pin "B6") (pinfunction "D+_B6") (pintype "bidirectional"))
    )
    (net (code "19") (name "D-") (class "Default")
      (node (ref "U3") (pin "23") (pinfunction "IO19/D-_23") (pintype "bidirectional"))
      (node (ref "X4") (pin "A7") (pinfunction "D-_A7") (pintype "bidirectional"))
      (node (ref "X4") (pin "B7") (pinfunction "D-_B7") (pintype "bidirectional"))
    )
    (net (code "20") (name "DATA0") (class "Default")
      (node (ref "X2") (pin "24") (pinfunction "DATA0_24") (pintype "output"))
    )
    (net (code "21") (name "DATA1") (class "Default")
      (node (ref "SJ3") (pin "1") (pinfunction "1_1") (pintype "passive"))
      (node (ref "X2") (pin "23") (pinfunction "DATA1_23") (pintype "output"))
    )
    (net (code "22") (name "DATA2") (class "Default")
      (node (ref "U3") (pin "17") (pinfunction "IO13_17") (pintype "bidirectional"))
      (node (ref "X2") (pin "19") (pinfunction "DATA2_19") (pintype "output"))
    )
    (net (code "23") (name "DATA3") (class "Default")
      (node (ref "U3") (pin "19") (pinfunction "IO15_19") (pintype "bidirectional"))
      (node (ref "X2") (pin "21") (pinfunction "DATA3_21") (pintype "output"))
    )
    (net (code "24") (name "DATA4") (class "Default")
      (node (ref "U3") (pin "20") (pinfunction "IO16_20") (pintype "bidirectional"))
      (node (ref "X2") (pin "22") (pinfunction "DATA4_22") (pintype "output"))
    )
    (net (code "25") (name "DATA5") (class "Default")
      (node (ref "U3") (pin "18") (pinfunction "IO14_18") (pintype "bidirectional"))
      (node (ref "X2") (pin "20") (pinfunction "DATA5_20") (pintype "output"))
    )
    (net (code "26") (name "DATA6") (class "Default")
      (node (ref "U3") (pin "16") (pinfunction "IO12_16") (pintype "bidirectional"))
      (node (ref "X2") (pin "18") (pinfunction "DATA6_18") (pintype "output"))
    )
    (net (code "27") (name "DATA7") (class "Default")
      (node (ref "U3") (pin "14") (pinfunction "IO10_14") (pintype "bidirectional"))
      (node (ref "X2") (pin "16") (pinfunction "DATA7_16") (pintype "output"))
    )
    (net (code "28") (name "DATA8") (class "Default")
      (node (ref "U3") (pin "13") (pinfunction "IO9_13") (pintype "bidirectional"))
      (node (ref "X2") (pin "14") (pinfunction "DATA8_14") (pintype "output"))
    )
    (net (code "29") (name "DATA9") (class "Default")
      (node (ref "U3") (pin "11") (pinfunction "IO7_11") (pintype "bidirectional"))
      (node (ref "X2") (pin "12") (pinfunction "DATA9_12") (pintype "output"))
    )
    (net (code "30") (name "DOWN") (class "Default")
      (node (ref "DOWN") (pin "2") (pinfunction "S_2") (pintype "passive"))
      (node (ref "IC3") (pin "17") (pinfunction "P1_7_17") (pintype "bidirectional"))
      (node (ref "R13") (pin "4") (pinfunction "1_4") (pintype "passive"))
    )
    (net (code "31") (name "EN") (class "Default")
      (node (ref "Q3") (pin "1") (pinfunction "G_1") (pintype "passive"))
      (node (ref "R12") (pin "2") (pinfunction "2_2") (pintype "passive"))
      (node (ref "SW4") (pin "B") (pinfunction "P_B") (pintype "passive"))
    )
    (net (code "32") (name "EXT_XCLK") (class "Default")
      (node (ref "U3") (pin "12") (pinfunction "IO8_12") (pintype "bidirectional"))
      (node (ref "X2") (pin "13") (pinfunction "XCLK_13") (pintype "input"))
    )
    (net (code "33") (name "GND") (class "Default")
      (node (ref "C1") (pin "2") (pinfunction "2_2") (pintype "passive"))
      (node (ref "C10") (pin "2") (pinfunction "2_2") (pintype "passive"))
      (node (ref "C11") (pin "2") (pinfunction "2_2") (pintype "passive"))
      (node (ref "C12") (pin "2") (pinfunction "2_2") (pintype "passive"))
      (node (ref "C13") (pin "2") (pinfunction "2_2") (pintype "passive"))
      (node (ref "C14") (pin "2") (pinfunction "2_2") (pintype "passive"))
      (node (ref "C15") (pin "2") (pinfunction "2_2") (pintype "passive"))
      (node (ref "C16") (pin "2") (pinfunction "2_2") (pintype "passive"))
      (node (ref "C17") (pin "2") (pinfunction "2_2") (pintype "passive"))
      (node (ref "C18") (pin "2") (pinfunction "2_2") (pintype "passive"))
      (node (ref "C19") (pin "2") (pinfunction "2_2") (pintype "passive"))
      (node (ref "C2") (pin "2") (pinfunction "2_2") (pintype "passive"))
      (node (ref "C20") (pin "2") (pinfunction "2_2") (pintype "passive"))
      (node (ref "C21") (pin "1") (pinfunction "1_1") (pintype "passive"))
      (node (ref "C22") (pin "2") (pinfunction "2_2") (pintype "passive"))
      (node (ref "C23") (pin "2") (pinfunction "2_2") (pintype "passive"))
      (node (ref "C25") (pin "2") (pinfunction "2_2") (pintype "passive"))
      (node (ref "C26") (pin "2") (pinfunction "2_2") (pintype "passive"))
      (node (ref "C27") (pin "2") (pinfunction "2_2") (pintype "passive"))
      (node (ref "C28") (pin "2") (pinfunction "2_2") (pintype "passive"))
      (node (ref "C29") (pin "2") (pinfunction "2_2") (pintype "passive"))
      (node (ref "C3") (pin "2") (pinfunction "2_2") (pintype "passive"))
      (node (ref "C30") (pin "2") (pinfunction "2_2") (pintype "passive"))
      (node (ref "C31") (pin "2") (pinfunction "2_2") (pintype "passive"))
      (node (ref "C32") (pin "2") (pinfunction "2_2") (pintype "passive"))
      (node (ref "C33") (pin "2") (pinfunction "2_2") (pintype "passive"))
      (node (ref "C34") (pin "2") (pinfunction "2_2") (pintype "passive"))
      (node (ref "C35") (pin "2") (pinfunction "2_2") (pintype "passive"))
      (node (ref "C36") (pin "2") (pinfunction "2_2") (pintype "passive"))
      (node (ref "C37") (pin "2") (pinfunction "2_2") (pintype "passive"))
      (node (ref "C38") (pin "1") (pinfunction "1_1") (pintype "passive"))
      (node (ref "C4") (pin "2") (pinfunction "2_2") (pintype "passive"))
      (node (ref "C40") (pin "2") (pinfunction "2_2") (pintype "passive"))
      (node (ref "C5") (pin "2") (pinfunction "2_2") (pintype "passive"))
      (node (ref "C6") (pin "2") (pinfunction "2_2") (pintype "passive"))
      (node (ref "C7") (pin "2") (pinfunction "2_2") (pintype "passive"))
      (node (ref "C8") (pin "2") (pinfunction "2_2") (pintype "passive"))
      (node (ref "C9") (pin "1") (pinfunction "1_1") (pintype "passive"))
      (node (ref "CONN1") (pin "1") (pinfunction "GND_1") (pintype "passive"))
      (node (ref "CONN1") (pin "MT1") (pinfunction "MT_MT1") (pintype "bidirectional"))
      (node (ref "CONN1") (pin "MT2") (pinfunction "MT_MT2") (pintype "bidirectional"))
      (node (ref "D1") (pin "A") (pinfunction "A_A") (pintype "passive"))
      (node (ref "D6") (pin "A") (pinfunction "A_A") (pintype "passive"))
      (node (ref "DOWN") (pin "1") (pinfunction "P_1") (pintype "passive"))
      (node (ref "FB1") (pin "1") (pinfunction "P$1_1") (pintype "passive"))
      (node (ref "IC2") (pin "2") (pinfunction "GND_2") (pintype "power_in"))
      (node (ref "IC3") (pin "18") (pinfunction "A0_18") (pintype "input"))
      (node (ref "IC3") (pin "24") (pinfunction "A1_24") (pintype "input"))
      (node (ref "IC3") (pin "9") (pinfunction "GND_9") (pintype "power_in"))
      (node (ref "IC3") (pin "THERM") (pinfunction "GND_THERM") (pintype "power_in"))
      (node (ref "IC4") (pin "10") (pinfunction "RES(GND)_10") (pintype "bidirectional"))
      (node (ref "IC4") (pin "12") (pinfunction "GND_12") (pintype "power_in"))
      (node (ref "IC4") (pin "5") (pinfunction "GND_5") (pintype "power_in"))
      (node (ref "LED2") (pin "4") (pinfunction "GND_4") (pintype "power_in"))
      (node (ref "LEFT") (pin "1") (pinfunction "P_1") (pintype "passive"))
      (node (ref "OK") (pin "1") (pinfunction "P_1") (pintype "passive"))
      (node (ref "ON") (pin "C") (pinfunction "C_C") (pintype "passive"))
      (node (ref "Q2") (pin "2") (pinfunction "S_2") (pintype "bidirectional"))
      (node (ref "R11") (pin "2") (pinfunction "2_2") (pintype "passive"))
      (node (ref "R14") (pin "1") (pinfunction "1_1") (pintype "passive"))
      (node (ref "R17") (pin "1") (pinfunction "1_1") (pintype "passive"))
      (node (ref "R2") (pin "1") (pinfunction "1_1") (pintype "passive"))
      (node (ref "R20") (pin "7") (pinfunction "2_7") (pintype "passive"))
      (node (ref "R21") (pin "1") (pinfunction "1_1") (pintype "passive"))
      (node (ref "R25") (pin "1") (pinfunction "1_1") (pintype "passive"))
      (node (ref "R27") (pin "2") (pinfunction "2_2") (pintype "passive"))
      (node (ref "R3") (pin "1") (pinfunction "1_1") (pintype "passive"))
      (node (ref "R8") (pin "1") (pinfunction "1_1") (pintype "passive"))
      (node (ref "RIGHT") (pin "1") (pinfunction "P_1") (pintype "passive"))
      (node (ref "SELECT") (pin "1") (pinfunction "P_1") (pintype "passive"))
      (node (ref "SENSE1") (pin "1") (pinfunction "1_1") (pintype "passive"))
      (node (ref "SENSE1") (pin "NC1") (pinfunction "MT_NC1") (pintype "bidirectional"))
      (node (ref "SENSE1") (pin "NC2") (pinfunction "MT_NC2") (pintype "bidirectional"))
      (node (ref "SENSE2") (pin "1") (pinfunction "1_1") (pintype "passive"))
      (node (ref "SENSE2") (pin "NC1") (pinfunction "MT_NC1") (pintype "bidirectional"))
      (node (ref "SENSE2") (pin "NC2") (pinfunction "MT_NC2") (pintype "bidirectional"))
      (node (ref "SW1") (pin "2") (pinfunction "S_2") (pintype "passive"))
      (node (ref "SW1") (pin "MT1") (pinfunction "MT_MT1") (pintype "bidirectional"))
      (node (ref "SW1") (pin "MT2") (pinfunction "MT_MT2") (pintype "bidirectional"))
      (node (ref "SW2") (pin "1") (pinfunction "P_1") (pintype "passive"))
      (node (ref "SW2") (pin "MT1") (pinfunction "MT_MT1") (pintype "bidirectional"))
      (node (ref "SW2") (pin "MT2") (pinfunction "MT_MT2") (pintype "bidirectional"))
      (node (ref "SW4") (pin "C") (pinfunction "S_C") (pintype "passive"))
      (node (ref "TFT1") (pin "10") (pinfunction "DB4_10") (pintype "bidirectional"))
      (node (ref "TFT1") (pin "11") (pinfunction "DB3_11") (pintype "bidirectional"))
      (node (ref "TFT1") (pin "12") (pinfunction "DB2_12") (pintype "bidirectional"))
      (node (ref "TFT1") (pin "13") (pinfunction "DB1_13") (pintype "bidirectional"))
      (node (ref "TFT1") (pin "14") (pinfunction "DB0_14") (pintype "bidirectional"))
      (node (ref "TFT1") (pin "15") (pinfunction "~{RD}_15") (pintype "input"))
      (node (ref "TFT1") (pin "22") (pinfunction "GND_22") (pintype "power_in"))
      (node (ref "TFT1") (pin "5") (pinfunction "IM0_5") (pintype "input"))
      (node (ref "TFT1") (pin "7") (pinfunction "DB7_7") (pintype "bidirectional"))
      (node (ref "TFT1") (pin "8") (pinfunction "DB6_8") (pintype "bidirectional"))
      (node (ref "TFT1") (pin "9") (pinfunction "DB5_9") (pintype "bidirectional"))
      (node (ref "TFT1") (pin "SUPPORT1") (pinfunction "GND_SUPPORT1") (pintype "power_in"))
      (node (ref "TFT1") (pin "SUPPORT2") (pinfunction "GND_SUPPORT2") (pintype "power_in"))
      (node (ref "TP3") (pin "P$1") (pinfunction "SEW_P$1") (pintype "bidirectional"))
      (node (ref "TP4") (pin "P$1") (pinfunction "SEW_P$1") (pintype "bidirectional"))
      (node (ref "TP5") (pin "P$1") (pinfunction "SEW_P$1") (pintype "bidirectional"))
      (node (ref "TP6") (pin "P$1") (pinfunction "SEW_P$1") (pintype "bidirectional"))
      (node (ref "U1") (pin "2") (pinfunction "GND_2") (pintype "power_in"))
      (node (ref "U2") (pin "2") (pinfunction "VSS_2") (pintype "power_in"))
      (node (ref "U3") (pin "1") (pinfunction "GND_1") (pintype "power_in"))
      (node (ref "U3") (pin "2") (pinfunction "GND_2") (pintype "power_in"))
      (node (ref "U3") (pin "42") (pinfunction "GND_42") (pintype "power_in"))
      (node (ref "U3") (pin "43") (pinfunction "GND_43") (pintype "power_in"))
      (node (ref "U3") (pin "46") (pinfunction "GND_46") (pintype "power_in"))
      (node (ref "U3") (pin "47") (pinfunction "GND_47") (pintype "power_in"))
      (node (ref "U3") (pin "48") (pinfunction "GND_48") (pintype "power_in"))
      (node (ref "U3") (pin "49") (pinfunction "GND_49") (pintype "power_in"))
      (node (ref "U3") (pin "50") (pinfunction "GND_50") (pintype "power_in"))
      (node (ref "U3") (pin "51") (pinfunction "GND_51") (pintype "power_in"))
      (node (ref "U3") (pin "52") (pinfunction "GND_52") (pintype "power_in"))
      (node (ref "U3") (pin "53") (pinfunction "GND_53") (pintype "power_in"))
      (node (ref "U3") (pin "54") (pinfunction "GND_54") (pintype "power_in"))
      (node (ref "U3") (pin "55") (pinfunction "GND_55") (pintype "power_in"))
      (node (ref "U3") (pin "56") (pinfunction "GND_56") (pintype "power_in"))
      (node (ref "U3") (pin "57") (pinfunction "GND_57") (pintype "power_in"))
      (node (ref "U3") (pin "58") (pinfunction "GND_58") (pintype "power_in"))
      (node (ref "U3") (pin "59") (pinfunction "GND_59") (pintype "power_in"))
      (node (ref "U3") (pin "60") (pinfunction "GND_60") (pintype "power_in"))
      (node (ref "U3") (pin "61") (pinfunction "EXP_61") (pintype "power_in"))
      (node (ref "U3") (pin "62") (pinfunction "GND_62") (pintype "power_in"))
      (node (ref "U3") (pin "63") (pinfunction "GND_63") (pintype "power_in"))
      (node (ref "U3") (pin "64") (pinfunction "GND_64") (pintype "power_in"))
      (node (ref "U3") (pin "65") (pinfunction "GND_65") (pintype "power_in"))
      (node (ref "U3") (pin "66") (pinfunction "EXP_66") (pintype "power_in"))
      (node (ref "U3") (pin "67") (pinfunction "EXP_67") (pintype "power_in"))
      (node (ref "U3") (pin "68") (pinfunction "EXP_68") (pintype "power_in"))
      (node (ref "U3") (pin "69") (pinfunction "EXP_69") (pintype "power_in"))
      (node (ref "U3") (pin "70") (pinfunction "EXP_70") (pintype "power_in"))
      (node (ref "U3") (pin "71") (pinfunction "EXP_71") (pintype "power_in"))
      (node (ref "U3") (pin "72") (pinfunction "EXP_72") (pintype "power_in"))
      (node (ref "U3") (pin "73") (pinfunction "EXP_73") (pintype "power_in"))
      (node (ref "U5") (pin "2") (pinfunction "GND_2") (pintype "power_in"))
      (node (ref "U6") (pin "7") (pinfunction "GND_7") (pintype "power_in"))
      (node (ref "U7") (pin "2") (pinfunction "GND_2") (pintype "power_in"))
      (node (ref "U7") (pin "3") (pinfunction "GND_3") (pintype "power_in"))
      (node (ref "UP") (pin "1") (pinfunction "P_1") (pintype "passive"))
      (node (ref "X1") (pin "1") (pinfunction "1_1") (pintype "passive"))
      (node (ref "X1") (pin "NC1") (pinfunction "P$1_NC1") (pintype "bidirectional"))
      (node (ref "X1") (pin "NC2") (pinfunction "P$1_NC2") (pintype "bidirectional"))
      (node (ref "X2") (pin "15") (pinfunction "DGND_15") (pintype "power_in"))
      (node (ref "X2") (pin "SPRT1") (pinfunction "DGND_SPRT1") (pintype "power_in"))
      (node (ref "X2") (pin "SPRT2") (pinfunction "DGND_SPRT2") (pintype "power_in"))
      (node (ref "X3") (pin "6") (pinfunction "SD_VSS_6") (pintype "power_in"))
      (node (ref "X3") (pin "MT1") (pinfunction "MOUNTING_MT1") (pintype "passive"))
      (node (ref "X3") (pin "MT2") (pinfunction "MOUNTING_MT2") (pintype "passive"))
      (node (ref "X4") (pin "A1B12") (pinfunction "GND_A1B12") (pintype "power_in"))
      (node (ref "X4") (pin "B1A12") (pinfunction "GND_B1A12") (pintype "power_in"))
    )
    (net (code "34") (name "HSYNC") (class "Default")
      (node (ref "U3") (pin "10") (pinfunction "IO6_10") (pintype "bidirectional"))
      (node (ref "X2") (pin "9") (pinfunction "HSYNC_9") (pintype "output"))
    )
    (net (code "35") (name "IO42_DBLTAP") (class "Default")
      (node (ref "C6") (pin "1") (pinfunction "1_1") (pintype "passive"))
      (node (ref "R17") (pin "2") (pinfunction "2_2") (pintype "passive"))
      (node (ref "U3") (pin "38") (pinfunction "IO42/TMS_38") (pintype "bidirectional"))
    )
    (net (code "36") (name "IRQ") (class "Default")
      (node (ref "IC3") (pin "22") (pinfunction "~{INT}_22") (pintype "output"))
      (node (ref "IC4") (pin "11") (pinfunction "INT1_11") (pintype "output"))
      (node (ref "U3") (pin "7") (pinfunction "IO3_7") (pintype "bidirectional"))
    )
    (net (code "37") (name "LED_K") (class "Default")
      (node (ref "R22") (pin "1") (pinfunction "1_1") (pintype "passive"))
      (node (ref "TFT1") (pin "2") (pinfunction "LEDK_2") (pintype "input"))
    )
    (net (code "38") (name "LEFT") (class "Default")
      (node (ref "IC3") (pin "16") (pinfunction "P1_6_16") (pintype "bidirectional"))
      (node (ref "LEFT") (pin "2") (pinfunction "S_2") (pintype "passive"))
      (node (ref "R13") (pin "1") (pinfunction "1_1") (pintype "passive"))
    )
    (net (code "39") (name "MIC") (class "Default")
      (node (ref "C41") (pin "2") (pinfunction "2_2") (pintype "passive"))
      (node (ref "R21") (pin "2") (pinfunction "2_2") (pintype "passive"))
      (node (ref "R9") (pin "1") (pinfunction "1_1") (pintype "passive"))
      (node (ref "U3") (pin "6") (pinfunction "IO2_6") (pintype "bidirectional"))
    )
    (net (code "40") (name "MISO") (class "Default")
      (node (ref "U3") (pin "33") (pinfunction "IO37_33") (pintype "bidirectional"))
      (node (ref "X3") (pin "7") (pinfunction "DATA_OUT_7") (pintype "output"))
    )
    (net (code "41") (name "MOSI") (class "Default")
      (node (ref "TFT1") (pin "21") (pinfunction "SDA_21") (pintype "bidirectional"))
      (node (ref "U3") (pin "31") (pinfunction "IO35_31") (pintype "input"))
      (node (ref "X3") (pin "3") (pinfunction "DATA_IN_3") (pintype "input"))
    )
    (net (code "42") (name "NEOPIXEL") (class "Default")
      (node (ref "LED2") (pin "1") (pinfunction "DI_1") (pintype "input"))
      (node (ref "U3") (pin "5") (pinfunction "IO1_5") (pintype "bidirectional"))
    )
    (net (code "43") (name "Net-(C21-Pad2)") (class "Default")
      (node (ref "C21") (pin "2") (pinfunction "2_2") (pintype "passive"))
      (node (ref "C39") (pin "2") (pinfunction "2_2") (pintype "passive"))
      (node (ref "R19") (pin "1") (pinfunction "1_1") (pintype "passive"))
    )
    (net (code "44") (name "Net-(C39-Pad1)") (class "Default")
      (node (ref "C39") (pin "1") (pinfunction "1_1") (pintype "passive"))
      (node (ref "R30") (pin "1") (pinfunction "1_1") (pintype "passive"))
    )
    (net (code "45") (name "Net-(C40-Pad1)") (class "Default")
      (node (ref "C40") (pin "1") (pinfunction "1_1") (pintype "passive"))
      (node (ref "R29") (pin "1") (pinfunction "1_1") (pintype "passive"))
    )
    (net (code "46") (name "Net-(CHG1-PadC)") (class "Default")
      (node (ref "CHG1") (pin "C") (pinfunction "C_C") (pintype "passive"))
      (node (ref "R4") (pin "2") (pinfunction "2_2") (pintype "passive"))
    )
    (net (code "47") (name "Net-(IC2-FB)") (class "Default")
      (node (ref "IC2") (pin "5") (pinfunction "FB_5") (pintype "power_in"))
      (node (ref "R24") (pin "1") (pinfunction "1_1") (pintype "passive"))
      (node (ref "R25") (pin "2") (pinfunction "2_2") (pintype "passive"))
    )
    (net (code "48") (name "Net-(IC2-SW)") (class "Default")
      (node (ref "IC2") (pin "3") (pinfunction "SW_3") (pintype "output"))
      (node (ref "L2") (pin "P$1") (pinfunction "1_P$1") (pintype "passive"))
    )
    (net (code "49") (name "Net-(ON-PadA)") (class "Default")
      (node (ref "ON") (pin "A") (pinfunction "A_A") (pintype "passive"))
      (node (ref "R6") (pin "1") (pinfunction "1_1") (pintype "passive"))
    )
    (net (code "50") (name "Net-(Q1-S)") (class "Default")
      (node (ref "D4") (pin "C") (pinfunction "C_C") (pintype "passive"))
      (node (ref "Q1") (pin "2") (pinfunction "S_2") (pintype "passive"))
      (node (ref "Q3") (pin "2") (pinfunction "S_2") (pintype "passive"))
      (node (ref "R12") (pin "1") (pinfunction "1_1") (pintype "passive"))
    )
    (net (code "51") (name "Net-(Q2-D)") (class "Default")
      (node (ref "Q2") (pin "3") (pinfunction "D_3") (pintype "bidirectional"))
      (node (ref "R22") (pin "2") (pinfunction "2_2") (pintype "passive"))
    )
    (net (code "52") (name "Net-(R16-Pad1)") (class "Default")
      (node (ref "R16") (pin "1") (pinfunction "1_1") (pintype "passive"))
      (node (ref "SENSE2") (pin "3") (pinfunction "3_3") (pintype "passive"))
    )
    (net (code "53") (name "Net-(R18-Pad1)") (class "Default")
      (node (ref "R18") (pin "1") (pinfunction "1_1") (pintype "passive"))
      (node (ref "SENSE1") (pin "3") (pinfunction "3_3") (pintype "passive"))
    )
    (net (code "54") (name "Net-(U2-PROG)") (class "Default")
      (node (ref "R2") (pin "2") (pinfunction "2_2") (pintype "passive"))
      (node (ref "U2") (pin "5") (pinfunction "PROG_5") (pintype "input"))
    )
    (net (code "55") (name "Net-(U2-STAT)") (class "Default")
      (node (ref "R4") (pin "1") (pinfunction "1_1") (pintype "passive"))
      (node (ref "U2") (pin "1") (pinfunction "STAT_1") (pintype "output"))
    )
    (net (code "56") (name "Net-(U6-IN_N)") (class "Default")
      (node (ref "R29") (pin "2") (pinfunction "2_2") (pintype "passive"))
      (node (ref "U6") (pin "4") (pinfunction "IN_N_4") (pintype "input"))
    )
    (net (code "57") (name "Net-(U6-IN_P)") (class "Default")
      (node (ref "R30") (pin "2") (pinfunction "2_2") (pintype "passive"))
      (node (ref "U6") (pin "3") (pinfunction "IN_P_3") (pintype "input"))
    )
    (net (code "58") (name "Net-(U6-VO_N)") (class "Default")
      (node (ref "SP1") (pin "-") (pinfunction "-_-") (pintype "passive"))
      (node (ref "U6") (pin "8") (pinfunction "VO_N_8") (pintype "output"))
    )
    (net (code "59") (name "Net-(U6-VO_P)") (class "Default")
      (node (ref "SP1") (pin "+") (pinfunction "+_+") (pintype "passive"))
      (node (ref "U6") (pin "5") (pinfunction "VO_P_5") (pintype "output"))
    )
    (net (code "60") (name "Net-(U7-OUTPUT)") (class "Default")
      (node (ref "C41") (pin "1") (pinfunction "1_1") (pintype "passive"))
      (node (ref "U7") (pin "4") (pinfunction "OUTPUT_4") (pintype "output"))
    )
    (net (code "61") (name "PCLK") (class "Default")
      (node (ref "C26") (pin "1") (pinfunction "1_1") (pintype "passive"))
      (node (ref "U3") (pin "15") (pinfunction "IO11_15") (pintype "bidirectional"))
      (node (ref "X2") (pin "17") (pinfunction "PCLK_17") (pintype "output"))
    )
    (net (code "62") (name "PERIPH_RST") (class "Default")
      (node (ref "IC3") (pin "23") (pinfunction "~{RST}_23") (pintype "input"))
      (node (ref "TFT1") (pin "20") (pinfunction "RESET_20") (pintype "input"))
      (node (ref "U3") (pin "34") (pinfunction "IO38_34") (pintype "bidirectional"))
    )
    (net (code "63") (name "RESET") (class "Default")
      (node (ref "C14") (pin "1") (pinfunction "1_1") (pintype "passive"))
      (node (ref "R1") (pin "1") (pinfunction "1_1") (pintype "passive"))
      (node (ref "SW2") (pin "2") (pinfunction "S_2") (pintype "passive"))
      (node (ref "TP2") (pin "P$1") (pinfunction "P$1_P$1") (pintype "bidirectional"))
      (node (ref "TP7") (pin "P$1") (pinfunction "P$1_P$1") (pintype "bidirectional"))
      (node (ref "U3") (pin "45") (pinfunction "EN_45") (pintype "input"))
    )
    (net (code "64") (name "RIGHT") (class "Default")
      (node (ref "IC3") (pin "14") (pinfunction "P1_4_14") (pintype "bidirectional"))
      (node (ref "R13") (pin "3") (pinfunction "1_3") (pintype "passive"))
      (node (ref "RIGHT") (pin "2") (pinfunction "S_2") (pintype "passive"))
    )
    (net (code "65") (name "RXD0") (class "Default")
      (node (ref "JP2") (pin "2") (pinfunction "2_2") (pintype "passive"))
      (node (ref "U3") (pin "40") (pinfunction "RXD0_40") (pintype "bidirectional"))
    )
    (net (code "66") (name "SCK") (class "Default")
      (node (ref "TFT1") (pin "17") (pinfunction "RS/CLK_17") (pintype "input"))
      (node (ref "U3") (pin "32") (pinfunction "IO36_32") (pintype "bidirectional"))
      (node (ref "X3") (pin "5") (pinfunction "SCLK_5") (pintype "input"))
    )
    (net (code "67") (name "SCL") (class "Default")
      (node (ref "CONN1") (pin "4") (pinfunction "SCL_4") (pintype "passive"))
      (node (ref "IC3") (pin "19") (pinfunction "SCL_19") (pintype "bidirectional"))
      (node (ref "IC4") (pin "4") (pinfunction "SCL_4") (pintype "bidirectional"))
      (node (ref "R5") (pin "2") (pinfunction "2_2") (pintype "passive"))
      (node (ref "U3") (pin "28") (pinfunction "IO33_28") (pintype "bidirectional"))
      (node (ref "X2") (pin "5") (pinfunction "SCL_5") (pintype "bidirectional"))
    )
    (net (code "68") (name "SDA") (class "Default")
      (node (ref "CONN1") (pin "3") (pinfunction "SDA_3") (pintype "passive"))
      (node (ref "IC3") (pin "20") (pinfunction "SDA_20") (pintype "bidirectional"))
      (node (ref "IC4") (pin "6") (pinfunction "SDA_6") (pintype "bidirectional"))
      (node (ref "R7") (pin "2") (pinfunction "2_2") (pintype "passive"))
      (node (ref "U3") (pin "29") (pinfunction "IO34_29") (pintype "input"))
      (node (ref "X2") (pin "3") (pinfunction "SDA_3") (pintype "bidirectional"))
    )
    (net (code "69") (name "SD_PWR") (class "Default")
      (node (ref "IC3") (pin "2") (pinfunction "P1_1_2") (pintype "bidirectional"))
      (node (ref "Q4") (pin "1") (pinfunction "G_1") (pintype "passive"))
      (node (ref "R26") (pin "2") (pinfunction "2_2") (pintype "passive"))
    )
    (net (code "70") (name "SD_VDD") (class "Default")
      (node (ref "C37") (pin "1") (pinfunction "1_1") (pintype "passive"))
      (node (ref "C38") (pin "2") (pinfunction "2_2") (pintype "passive"))
      (node (ref "Q4") (pin "3") (pinfunction "D_3") (pintype "passive"))
      (node (ref "X3") (pin "4") (pinfunction "SD_VDD_4") (pintype "power_in"))
    )
    (net (code "71") (name "SPKR") (class "Default")
      (node (ref "R19") (pin "2") (pinfunction "2_2") (pintype "passive"))
      (node (ref "U3") (pin "44") (pinfunction "IO46_DEBUGOUT_44") (pintype "input"))
    )
    (net (code "72") (name "SPKR_SD") (class "Default")
      (node (ref "IC3") (pin "5") (pinfunction "P0_0_5") (pintype "bidirectional"))
      (node (ref "R20") (pin "2") (pinfunction "1_2") (pintype "passive"))
      (node (ref "U6") (pin "1") (pinfunction "/SD_1") (pintype "input"))
    )
    (net (code "73") (name "TFT_CS") (class "Default")
      (node (ref "TFT1") (pin "18") (pinfunction "~{CS}_18") (pintype "input"))
      (node (ref "U3") (pin "35") (pinfunction "IO39/TCK_35") (pintype "bidirectional"))
    )
    (net (code "74") (name "TFT_DC") (class "Default")
      (node (ref "TFT1") (pin "16") (pinfunction "~{WR}/D~{C}_16") (pintype "input"))
      (node (ref "U3") (pin "36") (pinfunction "IO40/TDO_36") (pintype "bidirectional"))
    )
    (net (code "75") (name "TXD0") (class "Default")
      (node (ref "JP2") (pin "1") (pinfunction "1_1") (pintype "passive"))
      (node (ref "U3") (pin "39") (pinfunction "TXD0_39") (pintype "bidirectional"))
    )
    (net (code "76") (name "UP") (class "Default")
      (node (ref "IC3") (pin "15") (pinfunction "P1_5_15") (pintype "bidirectional"))
      (node (ref "R13") (pin "2") (pinfunction "1_2") (pintype "passive"))
      (node (ref "UP") (pin "2") (pinfunction "S_2") (pintype "passive"))
    )
    (net (code "77") (name "VBAT") (class "Default")
      (node (ref "C8") (pin "1") (pinfunction "1_1") (pintype "passive"))
      (node (ref "Q1") (pin "3") (pinfunction "D_3") (pintype "passive"))
      (node (ref "R10") (pin "1") (pinfunction "1_1") (pintype "passive"))
      (node (ref "U2") (pin "3") (pinfunction "VBAT_3") (pintype "power_in"))
      (node (ref "X1") (pin "2") (pinfunction "2_2") (pintype "passive"))
    )
    (net (code "78") (name "VBUS") (class "Default")
      (node (ref "C1") (pin "1") (pinfunction "1_1") (pintype "passive"))
      (node (ref "C15") (pin "1") (pinfunction "1_1") (pintype "passive"))
      (node (ref "CHG1") (pin "A") (pinfunction "A_A") (pintype "passive"))
      (node (ref "D4") (pin "A") (pinfunction "A_A") (pintype "passive"))
      (node (ref "Q1") (pin "1") (pinfunction "G_1") (pintype "passive"))
      (node (ref "R14") (pin "2") (pinfunction "2_2") (pintype "passive"))
      (node (ref "U2") (pin "4") (pinfunction "VDD_4") (pintype "power_in"))
      (node (ref "X4") (pin "A4B9") (pinfunction "VBUS_A4B9") (pintype "power_in"))
      (node (ref "X4") (pin "B4A9") (pinfunction "VBUS_B4A9") (pintype "power_in"))
    )
    (net (code "79") (name "VCC") (class "Default")
      (node (ref "C20") (pin "1") (pinfunction "1_1") (pintype "passive"))
      (node (ref "SENSE1") (pin "2") (pinfunction "2_2") (pintype "passive"))
      (node (ref "SENSE2") (pin "2") (pinfunction "2_2") (pintype "passive"))
      (node (ref "SJ2") (pin "2") (pinfunction "2_2") (pintype "passive"))
    )
    (net (code "80") (name "VHIGH") (class "Default")
      (node (ref "C11") (pin "1") (pinfunction "1_1") (pintype "passive"))
      (node (ref "C12") (pin "1") (pinfunction "1_1") (pintype "passive"))
      (node (ref "C3") (pin "1") (pinfunction "1_1") (pintype "passive"))
      (node (ref "C30") (pin "1") (pinfunction "1_1") (pintype "passive"))
      (node (ref "C31") (pin "1") (pinfunction "1_1") (pintype "passive"))
      (node (ref "IC2") (pin "1") (pinfunction "EN_1") (pintype "input"))
      (node (ref "IC2") (pin "4") (pinfunction "VIN_4") (pintype "power_in"))
      (node (ref "Q3") (pin "3") (pinfunction "D_3") (pintype "passive"))
      (node (ref "SJ1") (pin "3") (pinfunction "3_3") (pintype "passive"))
      (node (ref "SJ2") (pin "1") (pinfunction "1_1") (pintype "passive"))
      (node (ref "U6") (pin "6") (pinfunction "VDD_6") (pintype "power_in"))
    )
    (net (code "81") (name "VPWR") (class "Default")
      (node (ref "C19") (pin "1") (pinfunction "1_1") (pintype "passive"))
      (node (ref "C23") (pin "1") (pinfunction "1_1") (pintype "passive"))
      (node (ref "SJ1") (pin "2") (pinfunction "2_2") (pintype "passive"))
      (node (ref "U1") (pin "1") (pinfunction "IN_1") (pintype "power_in"))
      (node (ref "U1") (pin "3") (pinfunction "EN_3") (pintype "input"))
      (node (ref "U5") (pin "1") (pinfunction "IN_1") (pintype "power_in"))
      (node (ref "U5") (pin "3") (pinfunction "EN_3") (pintype "input"))
    )
    (net (code "82") (name "VSYNC") (class "Default")
      (node (ref "U3") (pin "9") (pinfunction "IO5_9") (pintype "bidirectional"))
      (node (ref "X2") (pin "7") (pinfunction "VSYNC_7") (pintype "output"))
    )
    (net (code "83") (name "unconnected-(IC3-P0_2-Pad7)") (class "Default")
      (node (ref "IC3") (pin "7") (pinfunction "P0_2_7") (pintype "bidirectional"))
    )
    (net (code "84") (name "unconnected-(IC3-P0_3-Pad8)") (class "Default")
      (node (ref "IC3") (pin "8") (pinfunction "P0_3_8") (pintype "bidirectional"))
    )
    (net (code "85") (name "unconnected-(IC3-P0_4-Pad10)") (class "Default")
      (node (ref "IC3") (pin "10") (pinfunction "P0_4_10") (pintype "bidirectional"))
    )
    (net (code "86") (name "unconnected-(IC3-P0_5-Pad11)") (class "Default")
      (node (ref "IC3") (pin "11") (pinfunction "P0_5_11") (pintype "bidirectional"))
    )
    (net (code "87") (name "unconnected-(IC3-P0_6-Pad12)") (class "Default")
      (node (ref "IC3") (pin "12") (pinfunction "P0_6_12") (pintype "bidirectional"))
    )
    (net (code "88") (name "unconnected-(IC3-P0_7-Pad13)") (class "Default")
      (node (ref "IC3") (pin "13") (pinfunction "P0_7_13") (pintype "bidirectional"))
    )
    (net (code "89") (name "unconnected-(IC3-P1_2-Pad3)") (class "Default")
      (node (ref "IC3") (pin "3") (pinfunction "P1_2_3") (pintype "bidirectional"))
    )
    (net (code "90") (name "unconnected-(IC4-INT2-Pad9)") (class "Default")
      (node (ref "IC4") (pin "9") (pinfunction "INT2_9") (pintype "output"))
    )
    (net (code "91") (name "unconnected-(IC4-NC-Pad2)") (class "Default")
      (node (ref "IC4") (pin "2") (pinfunction "NC_2") (pintype "no_connect"))
    )
    (net (code "92") (name "unconnected-(IC4-NC-Pad3)") (class "Default")
      (node (ref "IC4") (pin "3") (pinfunction "NC_3") (pintype "no_connect"))
    )
    (net (code "93") (name "unconnected-(LED2-DO-Pad3)") (class "Default")
      (node (ref "LED2") (pin "3") (pinfunction "DO_3") (pintype "output"))
    )
    (net (code "94") (name "unconnected-(SW4-O-PadA)") (class "Default")
      (node (ref "SW4") (pin "A") (pinfunction "O_A") (pintype "passive"))
    )
    (net (code "95") (name "unconnected-(TFT1-TE-Pad19)") (class "Default")
      (node (ref "TFT1") (pin "19") (pinfunction "TE_19") (pintype "output"))
    )
    (net (code "96") (name "unconnected-(U1-P4-Pad4)") (class "Default")
      (node (ref "U1") (pin "4") (pinfunction "P4_4") (pintype "bidirectional"))
    )
    (net (code "97") (name "unconnected-(U3-IO26-Pad26)") (class "Default")
      (node (ref "U3") (pin "26") (pinfunction "IO26_26") (pintype "bidirectional"))
    )
    (net (code "98") (name "unconnected-(U3-IO41{slash}TDI-Pad37)") (class "Default")
      (node (ref "U3") (pin "37") (pinfunction "IO41/TDI_37") (pintype "bidirectional"))
    )
    (net (code "99") (name "unconnected-(U5-P4-Pad4)") (class "Default")
      (node (ref "U5") (pin "4") (pinfunction "P4_4") (pintype "bidirectional"))
    )
    (net (code "100") (name "unconnected-(U6-NC-Pad2)") (class "Default")
      (node (ref "U6") (pin "2") (pinfunction "NC_2") (pintype "no_connect"))
    )
    (net (code "101") (name "unconnected-(X2-STROBE-Pad1)") (class "Default")
      (node (ref "X2") (pin "1") (pinfunction "STROBE_1") (pintype "input"))
    )
    (net (code "102") (name "unconnected-(X3-DAT1-Pad8)") (class "Default")
      (node (ref "X3") (pin "8") (pinfunction "DAT1_8") (pintype "bidirectional"))
    )
    (net (code "103") (name "unconnected-(X3-DAT2-Pad1)") (class "Default")
      (node (ref "X3") (pin "1") (pinfunction "DAT2_1") (pintype "bidirectional"))
    )
    (net (code "104") (name "unconnected-(X4-SBU1-PadA8)") (class "Default")
      (node (ref "X4") (pin "A8") (pinfunction "SBU1_A8") (pintype "bidirectional"))
    )
    (net (code "105") (name "unconnected-(X4-SBU2-PadB8)") (class "Default")
      (node (ref "X4") (pin "B8") (pinfunction "SBU2_B8") (pintype "bidirectional"))
    )
  )
)
